# LEDConverter.net
KiCad netlist of a schematic drawn in Altium Designer
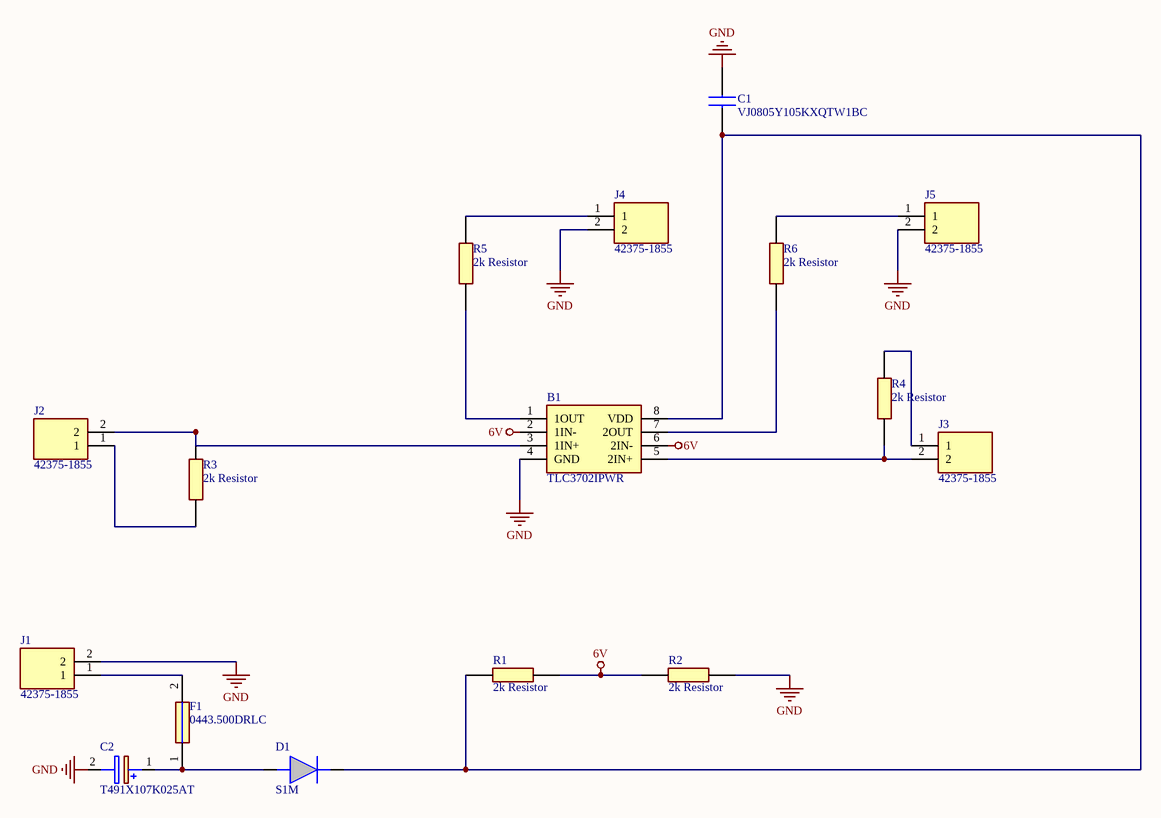
[diagram p0: LEDConverter.SchDoc]

(export (version "E")
  (design (tool "Eeschema 10.0.6"))
  (components
    (comp (ref "B1")
      (value "TLC3702IPWR")
      (footprint "SOP65P640X120-8N")
      (description "Texas Instruments TLC3702IPWR Dual Comparator, Push-Pull O/P, 5 V 8-Pin TSSOP")
      (fields (field (name "MOUSER PART NUMBER") "595-TLC3702IPWR"))
      (libsource (lib "TLC3702IPWR") (part "TLC3702IPWR"))
    )
    (comp (ref "C1")
      (value "VJ0805Y105KXQTW1BC")
      (footprint "CAPC2012X135N")
      (description "Multilayer Ceramic Capacitors MLCC - SMD/SMT 0805 1uF 10volts X7R 10%")
      (fields (field (name "MOUSER PART NUMBER") "77-VJ0805Y105KXQTBC"))
      (libsource (lib "VJ0805Y105KXQTW1BC") (part "VJ0805Y105KXQTW1BC"))
    )
    (comp (ref "C2")
      (value "T491X107K025AT")
      (footprint "SamacSys:T491X")
      (description "Capacitor Polarised")
      (fields (field (name "MOUSER PART NUMBER") "80-T491X107K025AT"))
      (libsource (lib "*") (part "T491X107K025AT"))
    )
    (comp (ref "D1")
      (value "S1M")
      (footprint "DIOM5227X270N")
      (description "Glass passivated junction.; Low profile package.")
      (fields (field (name "MOUSER PART NUMBER") "512-S1M"))
      (libsource (lib "S1M") (part "S1M"))
    )
    (comp (ref "F1")
      (value "0443.500DRLC")
      (footprint "SamacSys:0443500DR")
      (description "Fuse")
      (fields (field (name "MOUSER PART NUMBER") "576-0443.500DRLC"))
      (libsource (lib "*") (part "0443.500DRLC"))
    )
    (comp (ref "J1")
      (value "42375-1855")
      (footprint "HDRV2W87P0X254_1X2_768X249X1494P")
      (description "Headers & Wire Housings KK 100 Hdr Assy Bkw 02 Ckt Tin")
      (fields (field (name "MOUSER PART NUMBER") "538-42375-1855"))
      (libsource (lib "") (part "42375-1855_1"))
    )
    (comp (ref "J2")
      (value "42375-1855")
      (footprint "HDRV2W87P0X254_1X2_768X249X1494P")
      (description "Headers & Wire Housings KK 100 Hdr Assy Bkw 02 Ckt Tin")
      (fields (field (name "MOUSER PART NUMBER") "538-42375-1855"))
      (libsource (lib "") (part "42375-1855_1"))
    )
    (comp (ref "J3")
      (value "42375-1855")
      (footprint "HDRV2W87P0X254_1X2_768X249X1494P")
      (description "Headers & Wire Housings KK 100 Hdr Assy Bkw 02 Ckt Tin")
      (fields (field (name "MOUSER PART NUMBER") "538-42375-1855"))
      (libsource (lib "42375-1855") (part "42375-1855"))
    )
    (comp (ref "J4")
      (value "42375-1855")
      (footprint "HDRV2W87P0X254_1X2_768X249X1494P")
      (description "Headers & Wire Housings KK 100 Hdr Assy Bkw 02 Ckt Tin")
      (fields (field (name "MOUSER PART NUMBER") "538-42375-1855"))
      (libsource (lib "42375-1855") (part "42375-1855"))
    )
    (comp (ref "J5")
      (value "42375-1855")
      (footprint "HDRV2W87P0X254_1X2_768X249X1494P")
      (description "Headers & Wire Housings KK 100 Hdr Assy Bkw 02 Ckt Tin")
      (fields (field (name "MOUSER PART NUMBER") "538-42375-1855"))
      (libsource (lib "42375-1855") (part "42375-1855"))
    )
    (comp (ref "R1")
      (value "2k Resistor")
      (footprint "ERA6AEB101V")
      (description "Metal Thin Film Chip Resistor, 0805, 0.125W")
      (fields (field (name "MANUFACTURER_PART_NUMBER") "ERA-6AED4990V"))
      (libsource (lib "") (part "ERA-6AED4990V_1"))
    )
    (comp (ref "R2")
      (value "2k Resistor")
      (footprint "ERA6AEB101V")
      (description "Metal Thin Film Chip Resistor, 0805, 0.125W")
      (fields (field (name "MANUFACTURER_PART_NUMBER") "ERA-6AED4990V"))
      (libsource (lib "") (part "ERA-6AED4990V_1"))
    )
    (comp (ref "R3")
      (value "2k Resistor")
      (footprint "ERA6AEB101V")
      (description "Metal Thin Film Chip Resistor, 0805, 0.125W")
      (fields (field (name "MANUFACTURER_PART_NUMBER") "ERA-6AED4990V"))
      (libsource (lib "ERA-6AED4990V") (part "ERA-6AED4990V"))
    )
    (comp (ref "R4")
      (value "2k Resistor")
      (footprint "ERA6AEB101V")
      (description "Metal Thin Film Chip Resistor, 0805, 0.125W")
      (fields (field (name "MANUFACTURER_PART_NUMBER") "ERA-6AED4990V"))
      (libsource (lib "ERA-6AED4990V") (part "ERA-6AED4990V"))
    )
    (comp (ref "R5")
      (value "2k Resistor")
      (footprint "ERA6AEB101V")
      (description "Metal Thin Film Chip Resistor, 0805, 0.125W")
      (fields (field (name "MANUFACTURER_PART_NUMBER") "ERA-6AED4990V"))
      (libsource (lib "ERA-6AED4990V") (part "ERA-6AED4990V"))
    )
    (comp (ref "R6")
      (value "2k Resistor")
      (footprint "ERA6AEB101V")
      (description "Metal Thin Film Chip Resistor, 0805, 0.125W")
      (fields (field (name "MANUFACTURER_PART_NUMBER") "ERA-6AED4990V"))
      (libsource (lib "ERA-6AED4990V") (part "ERA-6AED4990V"))
    )
  )
  (nets
    (net (code "1") (name "6V") (class "Default")
      (node (ref "B1") (pin "2") (pinfunction "1IN-_2") (pintype "passive"))
      (node (ref "B1") (pin "6") (pinfunction "2IN-_6") (pintype "passive"))
      (node (ref "R1") (pin "2") (pinfunction "2_2") (pintype "passive"))
      (node (ref "R2") (pin "1") (pinfunction "1_1") (pintype "passive"))
    )
    (net (code "2") (name "GND") (class "Default")
      (node (ref "B1") (pin "4") (pinfunction "GND_4") (pintype "passive"))
      (node (ref "C1") (pin "2") (pinfunction "2_2") (pintype "passive"))
      (node (ref "C2") (pin "2") (pinfunction "-_2") (pintype "passive"))
      (node (ref "J1") (pin "2") (pinfunction "2_2") (pintype "passive"))
      (node (ref "J4") (pin "2") (pinfunction "2_2") (pintype "passive"))
      (node (ref "J5") (pin "2") (pinfunction "2_2") (pintype "passive"))
      (node (ref "R2") (pin "2") (pinfunction "2_2") (pintype "passive"))
    )
    (net (code "3") (name "Net-(B1-1IN+)") (class "Default")
      (node (ref "B1") (pin "3") (pinfunction "1IN+_3") (pintype "passive"))
      (node (ref "J2") (pin "2") (pinfunction "2_2") (pintype "passive"))
      (node (ref "R3") (pin "2") (pinfunction "2_2") (pintype "passive"))
    )
    (net (code "4") (name "Net-(B1-1OUT)") (class "Default")
      (node (ref "B1") (pin "1") (pinfunction "1OUT_1") (pintype "passive"))
      (node (ref "R5") (pin "1") (pinfunction "1_1") (pintype "passive"))
    )
    (net (code "5") (name "Net-(B1-2IN+)") (class "Default")
      (node (ref "B1") (pin "5") (pinfunction "2IN+_5") (pintype "passive"))
      (node (ref "J3") (pin "2") (pinfunction "2_2") (pintype "passive"))
      (node (ref "R4") (pin "1") (pinfunction "1_1") (pintype "passive"))
    )
    (net (code "6") (name "Net-(B1-2OUT)") (class "Default")
      (node (ref "B1") (pin "7") (pinfunction "2OUT_7") (pintype "passive"))
      (node (ref "R6") (pin "1") (pinfunction "1_1") (pintype "passive"))
    )
    (net (code "7") (name "Net-(B1-VDD)") (class "Default")
      (node (ref "B1") (pin "8") (pinfunction "VDD_8") (pintype "passive"))
      (node (ref "C1") (pin "1") (pinfunction "1_1") (pintype "passive"))
      (node (ref "D1") (pin "1") (pinfunction "K_1") (pintype "passive"))
      (node (ref "R1") (pin "1") (pinfunction "1_1") (pintype "passive"))
    )
    (net (code "8") (name "Net-(C2-+)") (class "Default")
      (node (ref "C2") (pin "1") (pinfunction "+_1") (pintype "passive"))
      (node (ref "D1") (pin "2") (pinfunction "A_2") (pintype "passive"))
      (node (ref "F1") (pin "1") (pinfunction "1_1") (pintype "passive"))
    )
    (net (code "9") (name "Net-(F1-Pad2)") (class "Default")
      (node (ref "F1") (pin "2") (pinfunction "2_2") (pintype "passive"))
      (node (ref "J1") (pin "1") (pinfunction "1_1") (pintype "passive"))
    )
    (net (code "10") (name "Net-(J2-Pad1)") (class "Default")
      (node (ref "J2") (pin "1") (pinfunction "1_1") (pintype "passive"))
      (node (ref "R3") (pin "1") (pinfunction "1_1") (pintype "passive"))
    )
    (net (code "11") (name "Net-(J3-Pad1)") (class "Default")
      (node (ref "J3") (pin "1") (pinfunction "1_1") (pintype "passive"))
      (node (ref "R4") (pin "2") (pinfunction "2_2") (pintype "passive"))
    )
    (net (code "12") (name "Net-(J4-Pad1)") (class "Default")
      (node (ref "J4") (pin "1") (pinfunction "1_1") (pintype "passive"))
      (node (ref "R5") (pin "2") (pinfunction "2_2") (pintype "passive"))
    )
    (net (code "13") (name "Net-(J5-Pad1)") (class "Default")
      (node (ref "J5") (pin "1") (pinfunction "1_1") (pintype "passive"))
      (node (ref "R6") (pin "2") (pinfunction "2_2") (pintype "passive"))
    )
  )
)
